# OLEDHAT.net
KiCad netlist of a schematic drawn in EAGLE
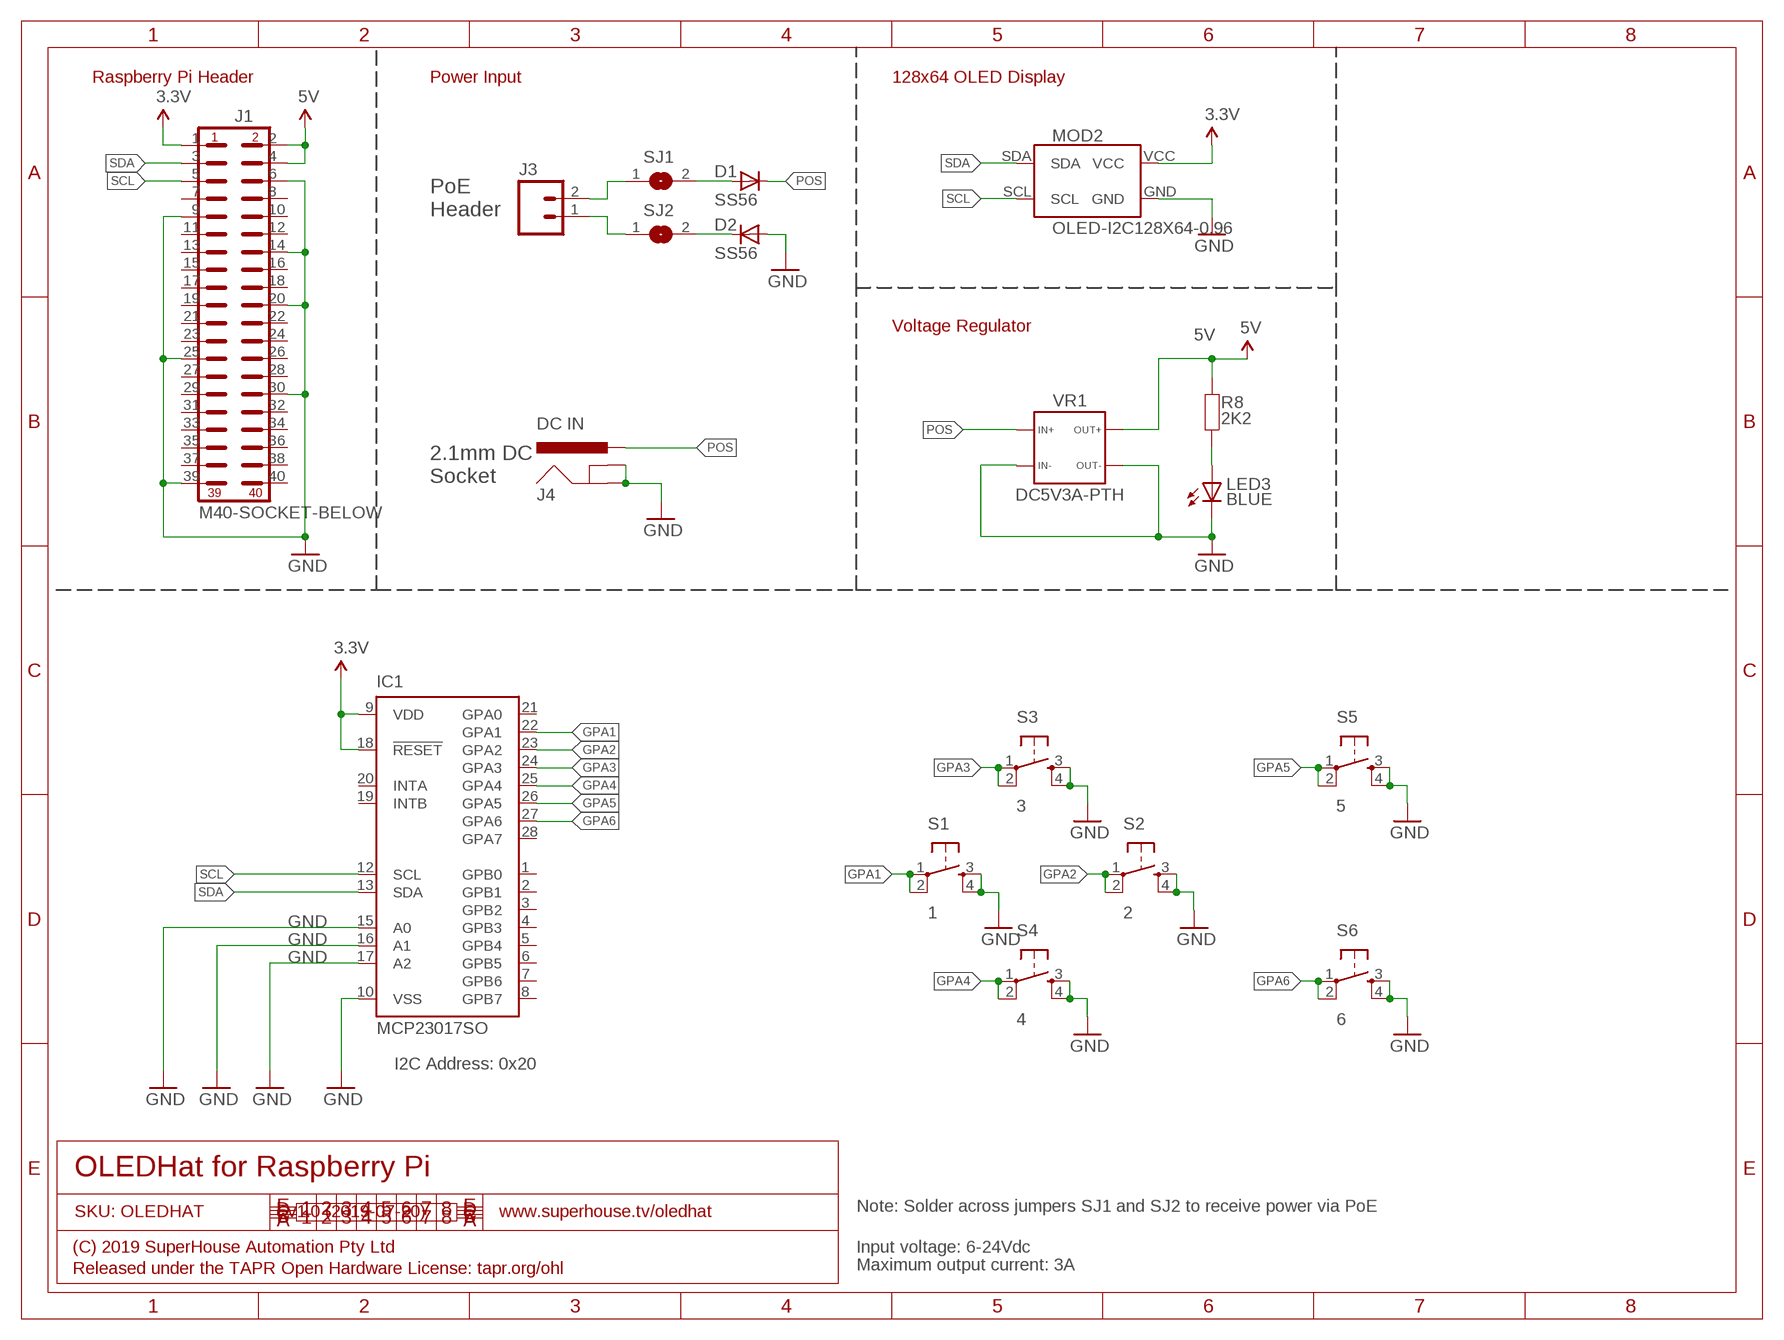
[diagram p0: schematic, sheet 1]

(export (version "E")
  (design (tool "Eeschema 10.0.6"))
  (components
    (comp (ref "D1")
      (value "SS56")
      (footprint "eagle-import:SMA-DIODE")
      (libsource (lib "eagle-import") (part "DIODESMA"))
    )
    (comp (ref "D2")
      (value "SS56")
      (footprint "eagle-import:SMA-DIODE")
      (libsource (lib "eagle-import") (part "DIODESMA"))
    )
    (comp (ref "IC1")
      (value "MCP23017SO")
      (footprint "eagle-import:SO28W")
      (libsource (lib "eagle-import") (part "MCP23017SO"))
    )
    (comp (ref "J1")
      (value "M40-SOCKET-BELOW")
      (footprint "eagle-import:2X20-S-BELOW")
      (libsource (lib "eagle-import") (part "M40-SOCKET-BELOW"))
    )
    (comp (ref "J3")
      (value "M02-SOCKET-BELOW")
      (footprint "eagle-import:1X02-S-BELOW")
      (libsource (lib "eagle-import") (part "M02-SOCKET-BELOW"))
    )
    (comp (ref "J4")
      (value "DC IN")
      (footprint "eagle-import:POWER_JACK_SLOTS")
      (libsource (lib "eagle-import") (part "POWER_JACK-SLOTS"))
    )
    (comp (ref "LED3")
      (value "BLUE")
      (footprint "eagle-import:LED-0603")
      (libsource (lib "eagle-import") (part "LED0603"))
    )
    (comp (ref "MOD2")
      (value "OLED-I2C128X64-0.96")
      (footprint "eagle-import:OLED-128X64-0.96")
      (libsource (lib "eagle-import") (part "OLED-I2C128X64-0.96"))
    )
    (comp (ref "R8")
      (value "2K2")
      (footprint "eagle-import:R0603")
      (libsource (lib "eagle-import") (part "RESISTOR0603"))
    )
    (comp (ref "S1")
      (value "1")
      (footprint "eagle-import:TACTILE-PTH-4.5MM")
      (libsource (lib "eagle-import") (part "TAC_SWITCH4.5"))
    )
    (comp (ref "S2")
      (value "2")
      (footprint "eagle-import:TACTILE-PTH-4.5MM")
      (libsource (lib "eagle-import") (part "TAC_SWITCH4.5"))
    )
    (comp (ref "S3")
      (value "3")
      (footprint "eagle-import:TACTILE-PTH-4.5MM")
      (libsource (lib "eagle-import") (part "TAC_SWITCH4.5"))
    )
    (comp (ref "S4")
      (value "4")
      (footprint "eagle-import:TACTILE-PTH-4.5MM")
      (libsource (lib "eagle-import") (part "TAC_SWITCH4.5"))
    )
    (comp (ref "S5")
      (value "5")
      (footprint "eagle-import:TACTILE-PTH-4.5MM")
      (libsource (lib "eagle-import") (part "TAC_SWITCH4.5"))
    )
    (comp (ref "S6")
      (value "6")
      (footprint "eagle-import:TACTILE-PTH-4.5MM")
      (libsource (lib "eagle-import") (part "TAC_SWITCH4.5"))
    )
    (comp (ref "SJ1")
      (value "SJN")
      (footprint "eagle-import:SJ")
      (libsource (lib "eagle-import") (part "SJN"))
    )
    (comp (ref "SJ2")
      (value "SJN")
      (footprint "eagle-import:SJ")
      (libsource (lib "eagle-import") (part "SJN"))
    )
    (comp (ref "VR1")
      (value "DC5V3A-PTH")
      (footprint "eagle-import:DC5V3A-PTH")
      (libsource (lib "eagle-import") (part "DC5V3A-PTH"))
    )
  )
  (nets
    (net (code "1") (name "3.3V") (class "Default")
      (node (ref "IC1") (pin "18") (pinfunction "~{RESET}_18") (pintype "input"))
      (node (ref "IC1") (pin "9") (pinfunction "VDD_9") (pintype "power_in"))
      (node (ref "J1") (pin "1") (pinfunction "1_1") (pintype "passive"))
      (node (ref "MOD2") (pin "VCC") (pinfunction "VCC_VCC") (pintype "bidirectional"))
    )
    (net (code "2") (name "5V") (class "Default")
      (node (ref "J1") (pin "2") (pinfunction "2_2") (pintype "passive"))
      (node (ref "J1") (pin "4") (pinfunction "4_4") (pintype "passive"))
      (node (ref "R8") (pin "1") (pinfunction "1_1") (pintype "passive"))
      (node (ref "VR1") (pin "3A") (pinfunction "3_3A") (pintype "bidirectional"))
      (node (ref "VR1") (pin "3B") (pinfunction "3_3B") (pintype "bidirectional"))
    )
    (net (code "3") (name "GND") (class "Default")
      (node (ref "D2") (pin "A") (pinfunction "A_A") (pintype "passive"))
      (node (ref "IC1") (pin "10") (pinfunction "VSS_10") (pintype "power_in"))
      (node (ref "IC1") (pin "15") (pinfunction "A0_15") (pintype "input"))
      (node (ref "IC1") (pin "16") (pinfunction "A1_16") (pintype "input"))
      (node (ref "IC1") (pin "17") (pinfunction "A2_17") (pintype "input"))
      (node (ref "J1") (pin "14") (pinfunction "14_14") (pintype "passive"))
      (node (ref "J1") (pin "20") (pinfunction "20_20") (pintype "passive"))
      (node (ref "J1") (pin "25") (pinfunction "25_25") (pintype "passive"))
      (node (ref "J1") (pin "30") (pinfunction "30_30") (pintype "passive"))
      (node (ref "J1") (pin "39") (pinfunction "39_39") (pintype "passive"))
      (node (ref "J1") (pin "6") (pinfunction "6_6") (pintype "passive"))
      (node (ref "J1") (pin "9") (pinfunction "9_9") (pintype "passive"))
      (node (ref "J4") (pin "GND") (pinfunction "GND_GND") (pintype "bidirectional"))
      (node (ref "J4") (pin "GNDBREAK") (pinfunction "GNDBREAK_GNDBREAK") (pintype "bidirectional"))
      (node (ref "LED3") (pin "C") (pinfunction "C_C") (pintype "passive"))
      (node (ref "MOD2") (pin "GND") (pinfunction "GND_GND") (pintype "bidirectional"))
      (node (ref "S1") (pin "3") (pinfunction "3_3") (pintype "passive"))
      (node (ref "S1") (pin "4") (pinfunction "4_4") (pintype "passive"))
      (node (ref "S2") (pin "3") (pinfunction "3_3") (pintype "passive"))
      (node (ref "S2") (pin "4") (pinfunction "4_4") (pintype "passive"))
      (node (ref "S3") (pin "3") (pinfunction "3_3") (pintype "passive"))
      (node (ref "S3") (pin "4") (pinfunction "4_4") (pintype "passive"))
      (node (ref "S4") (pin "3") (pinfunction "3_3") (pintype "passive"))
      (node (ref "S4") (pin "4") (pinfunction "4_4") (pintype "passive"))
      (node (ref "S5") (pin "3") (pinfunction "3_3") (pintype "passive"))
      (node (ref "S5") (pin "4") (pinfunction "4_4") (pintype "passive"))
      (node (ref "S6") (pin "3") (pinfunction "3_3") (pintype "passive"))
      (node (ref "S6") (pin "4") (pinfunction "4_4") (pintype "passive"))
      (node (ref "VR1") (pin "1A") (pinfunction "1_1A") (pintype "bidirectional"))
      (node (ref "VR1") (pin "1B") (pinfunction "1_1B") (pintype "bidirectional"))
      (node (ref "VR1") (pin "4A") (pinfunction "4_4A") (pintype "bidirectional"))
      (node (ref "VR1") (pin "4B") (pinfunction "4_4B") (pintype "bidirectional"))
    )
    (net (code "4") (name "GPA1") (class "Default")
      (node (ref "IC1") (pin "22") (pinfunction "GPA1_22") (pintype "bidirectional"))
      (node (ref "S1") (pin "1") (pinfunction "1_1") (pintype "passive"))
      (node (ref "S1") (pin "2") (pinfunction "2_2") (pintype "passive"))
    )
    (net (code "5") (name "GPA2") (class "Default")
      (node (ref "IC1") (pin "23") (pinfunction "GPA2_23") (pintype "bidirectional"))
      (node (ref "S2") (pin "1") (pinfunction "1_1") (pintype "passive"))
      (node (ref "S2") (pin "2") (pinfunction "2_2") (pintype "passive"))
    )
    (net (code "6") (name "GPA3") (class "Default")
      (node (ref "IC1") (pin "24") (pinfunction "GPA3_24") (pintype "bidirectional"))
      (node (ref "S3") (pin "1") (pinfunction "1_1") (pintype "passive"))
      (node (ref "S3") (pin "2") (pinfunction "2_2") (pintype "passive"))
    )
    (net (code "7") (name "GPA4") (class "Default")
      (node (ref "IC1") (pin "25") (pinfunction "GPA4_25") (pintype "bidirectional"))
      (node (ref "S4") (pin "1") (pinfunction "1_1") (pintype "passive"))
      (node (ref "S4") (pin "2") (pinfunction "2_2") (pintype "passive"))
    )
    (net (code "8") (name "GPA5") (class "Default")
      (node (ref "IC1") (pin "26") (pinfunction "GPA5_26") (pintype "bidirectional"))
      (node (ref "S5") (pin "1") (pinfunction "1_1") (pintype "passive"))
      (node (ref "S5") (pin "2") (pinfunction "2_2") (pintype "passive"))
    )
    (net (code "9") (name "GPA6") (class "Default")
      (node (ref "IC1") (pin "27") (pinfunction "GPA6_27") (pintype "bidirectional"))
      (node (ref "S6") (pin "1") (pinfunction "1_1") (pintype "passive"))
      (node (ref "S6") (pin "2") (pinfunction "2_2") (pintype "passive"))
    )
    (net (code "10") (name "Net-(D1-PadA)") (class "Default")
      (node (ref "D1") (pin "A") (pinfunction "A_A") (pintype "passive"))
      (node (ref "SJ1") (pin "2") (pinfunction "2_2") (pintype "passive"))
    )
    (net (code "11") (name "Net-(D2-PadC)") (class "Default")
      (node (ref "D2") (pin "C") (pinfunction "C_C") (pintype "passive"))
      (node (ref "SJ2") (pin "2") (pinfunction "2_2") (pintype "passive"))
    )
    (net (code "12") (name "Net-(J3-Pad1)") (class "Default")
      (node (ref "J3") (pin "1") (pinfunction "1_1") (pintype "passive"))
      (node (ref "SJ2") (pin "1") (pinfunction "1_1") (pintype "passive"))
    )
    (net (code "13") (name "Net-(J3-Pad2)") (class "Default")
      (node (ref "J3") (pin "2") (pinfunction "2_2") (pintype "passive"))
      (node (ref "SJ1") (pin "1") (pinfunction "1_1") (pintype "passive"))
    )
    (net (code "14") (name "Net-(LED3-PadA)") (class "Default")
      (node (ref "LED3") (pin "A") (pinfunction "A_A") (pintype "passive"))
      (node (ref "R8") (pin "2") (pinfunction "2_2") (pintype "passive"))
    )
    (net (code "15") (name "POS") (class "Default")
      (node (ref "D1") (pin "C") (pinfunction "C_C") (pintype "passive"))
      (node (ref "J4") (pin "PWR") (pinfunction "PWR_PWR") (pintype "bidirectional"))
      (node (ref "VR1") (pin "2A") (pinfunction "2_2A") (pintype "bidirectional"))
      (node (ref "VR1") (pin "2B") (pinfunction "2_2B") (pintype "bidirectional"))
    )
    (net (code "16") (name "SCL") (class "Default")
      (node (ref "IC1") (pin "12") (pinfunction "SCL_12") (pintype "input"))
      (node (ref "J1") (pin "5") (pinfunction "5_5") (pintype "passive"))
      (node (ref "MOD2") (pin "SCL") (pinfunction "SCL_SCL") (pintype "bidirectional"))
    )
    (net (code "17") (name "SDA") (class "Default")
      (node (ref "IC1") (pin "13") (pinfunction "SDA_13") (pintype "bidirectional"))
      (node (ref "J1") (pin "3") (pinfunction "3_3") (pintype "passive"))
      (node (ref "MOD2") (pin "SDA") (pinfunction "SDA_SDA") (pintype "bidirectional"))
    )
    (net (code "18") (name "unconnected-(IC1-GPA0-Pad21)") (class "Default")
      (node (ref "IC1") (pin "21") (pinfunction "GPA0_21") (pintype "bidirectional"))
    )
    (net (code "19") (name "unconnected-(IC1-GPA7-Pad28)") (class "Default")
      (node (ref "IC1") (pin "28") (pinfunction "GPA7_28") (pintype "bidirectional"))
    )
    (net (code "20") (name "unconnected-(IC1-GPB0-Pad1)") (class "Default")
      (node (ref "IC1") (pin "1") (pinfunction "GPB0_1") (pintype "bidirectional"))
    )
    (net (code "21") (name "unconnected-(IC1-GPB1-Pad2)") (class "Default")
      (node (ref "IC1") (pin "2") (pinfunction "GPB1_2") (pintype "bidirectional"))
    )
    (net (code "22") (name "unconnected-(IC1-GPB2-Pad3)") (class "Default")
      (node (ref "IC1") (pin "3") (pinfunction "GPB2_3") (pintype "bidirectional"))
    )
    (net (code "23") (name "unconnected-(IC1-GPB3-Pad4)") (class "Default")
      (node (ref "IC1") (pin "4") (pinfunction "GPB3_4") (pintype "bidirectional"))
    )
    (net (code "24") (name "unconnected-(IC1-GPB4-Pad5)") (class "Default")
      (node (ref "IC1") (pin "5") (pinfunction "GPB4_5") (pintype "bidirectional"))
    )
    (net (code "25") (name "unconnected-(IC1-GPB5-Pad6)") (class "Default")
      (node (ref "IC1") (pin "6") (pinfunction "GPB5_6") (pintype "bidirectional"))
    )
    (net (code "26") (name "unconnected-(IC1-GPB6-Pad7)") (class "Default")
      (node (ref "IC1") (pin "7") (pinfunction "GPB6_7") (pintype "bidirectional"))
    )
    (net (code "27") (name "unconnected-(IC1-GPB7-Pad8)") (class "Default")
      (node (ref "IC1") (pin "8") (pinfunction "GPB7_8") (pintype "bidirectional"))
    )
    (net (code "28") (name "unconnected-(IC1-INTA-Pad20)") (class "Default")
      (node (ref "IC1") (pin "20") (pinfunction "INTA_20") (pintype "output"))
    )
    (net (code "29") (name "unconnected-(IC1-INTB-Pad19)") (class "Default")
      (node (ref "IC1") (pin "19") (pinfunction "INTB_19") (pintype "output"))
    )
    (net (code "30") (name "unconnected-(J1-Pad7)") (class "Default")
      (node (ref "J1") (pin "7") (pinfunction "7_7") (pintype "passive"))
    )
    (net (code "31") (name "unconnected-(J1-Pad8)") (class "Default")
      (node (ref "J1") (pin "8") (pinfunction "8_8") (pintype "passive"))
    )
    (net (code "32") (name "unconnected-(J1-Pad10)") (class "Default")
      (node (ref "J1") (pin "10") (pinfunction "10_10") (pintype "passive"))
    )
    (net (code "33") (name "unconnected-(J1-Pad11)") (class "Default")
      (node (ref "J1") (pin "11") (pinfunction "11_11") (pintype "passive"))
    )
    (net (code "34") (name "unconnected-(J1-Pad12)") (class "Default")
      (node (ref "J1") (pin "12") (pinfunction "12_12") (pintype "passive"))
    )
    (net (code "35") (name "unconnected-(J1-Pad13)") (class "Default")
      (node (ref "J1") (pin "13") (pinfunction "13_13") (pintype "passive"))
    )
    (net (code "36") (name "unconnected-(J1-Pad15)") (class "Default")
      (node (ref "J1") (pin "15") (pinfunction "15_15") (pintype "passive"))
    )
    (net (code "37") (name "unconnected-(J1-Pad16)") (class "Default")
      (node (ref "J1") (pin "16") (pinfunction "16_16") (pintype "passive"))
    )
    (net (code "38") (name "unconnected-(J1-Pad17)") (class "Default")
      (node (ref "J1") (pin "17") (pinfunction "17_17") (pintype "passive"))
    )
    (net (code "39") (name "unconnected-(J1-Pad18)") (class "Default")
      (node (ref "J1") (pin "18") (pinfunction "18_18") (pintype "passive"))
    )
    (net (code "40") (name "unconnected-(J1-Pad19)") (class "Default")
      (node (ref "J1") (pin "19") (pinfunction "19_19") (pintype "passive"))
    )
    (net (code "41") (name "unconnected-(J1-Pad21)") (class "Default")
      (node (ref "J1") (pin "21") (pinfunction "21_21") (pintype "passive"))
    )
    (net (code "42") (name "unconnected-(J1-Pad22)") (class "Default")
      (node (ref "J1") (pin "22") (pinfunction "22_22") (pintype "passive"))
    )
    (net (code "43") (name "unconnected-(J1-Pad23)") (class "Default")
      (node (ref "J1") (pin "23") (pinfunction "23_23") (pintype "passive"))
    )
    (net (code "44") (name "unconnected-(J1-Pad24)") (class "Default")
      (node (ref "J1") (pin "24") (pinfunction "24_24") (pintype "passive"))
    )
    (net (code "45") (name "unconnected-(J1-Pad26)") (class "Default")
      (node (ref "J1") (pin "26") (pinfunction "26_26") (pintype "passive"))
    )
    (net (code "46") (name "unconnected-(J1-Pad27)") (class "Default")
      (node (ref "J1") (pin "27") (pinfunction "27_27") (pintype "passive"))
    )
    (net (code "47") (name "unconnected-(J1-Pad28)") (class "Default")
      (node (ref "J1") (pin "28") (pinfunction "28_28") (pintype "passive"))
    )
    (net (code "48") (name "unconnected-(J1-Pad29)") (class "Default")
      (node (ref "J1") (pin "29") (pinfunction "29_29") (pintype "passive"))
    )
    (net (code "49") (name "unconnected-(J1-Pad31)") (class "Default")
      (node (ref "J1") (pin "31") (pinfunction "31_31") (pintype "passive"))
    )
    (net (code "50") (name "unconnected-(J1-Pad32)") (class "Default")
      (node (ref "J1") (pin "32") (pinfunction "32_32") (pintype "passive"))
    )
    (net (code "51") (name "unconnected-(J1-Pad33)") (class "Default")
      (node (ref "J1") (pin "33") (pinfunction "33_33") (pintype "passive"))
    )
    (net (code "52") (name "unconnected-(J1-Pad34)") (class "Default")
      (node (ref "J1") (pin "34") (pinfunction "34_34") (pintype "passive"))
    )
    (net (code "53") (name "unconnected-(J1-Pad35)") (class "Default")
      (node (ref "J1") (pin "35") (pinfunction "35_35") (pintype "passive"))
    )
    (net (code "54") (name "unconnected-(J1-Pad36)") (class "Default")
      (node (ref "J1") (pin "36") (pinfunction "36_36") (pintype "passive"))
    )
    (net (code "55") (name "unconnected-(J1-Pad37)") (class "Default")
      (node (ref "J1") (pin "37") (pinfunction "37_37") (pintype "passive"))
    )
    (net (code "56") (name "unconnected-(J1-Pad38)") (class "Default")
      (node (ref "J1") (pin "38") (pinfunction "38_38") (pintype "passive"))
    )
    (net (code "57") (name "unconnected-(J1-Pad40)") (class "Default")
      (node (ref "J1") (pin "40") (pinfunction "40_40") (pintype "passive"))
    )
  )
)
